# untitle2.net
KiCad netlist of a schematic drawn in EAGLE
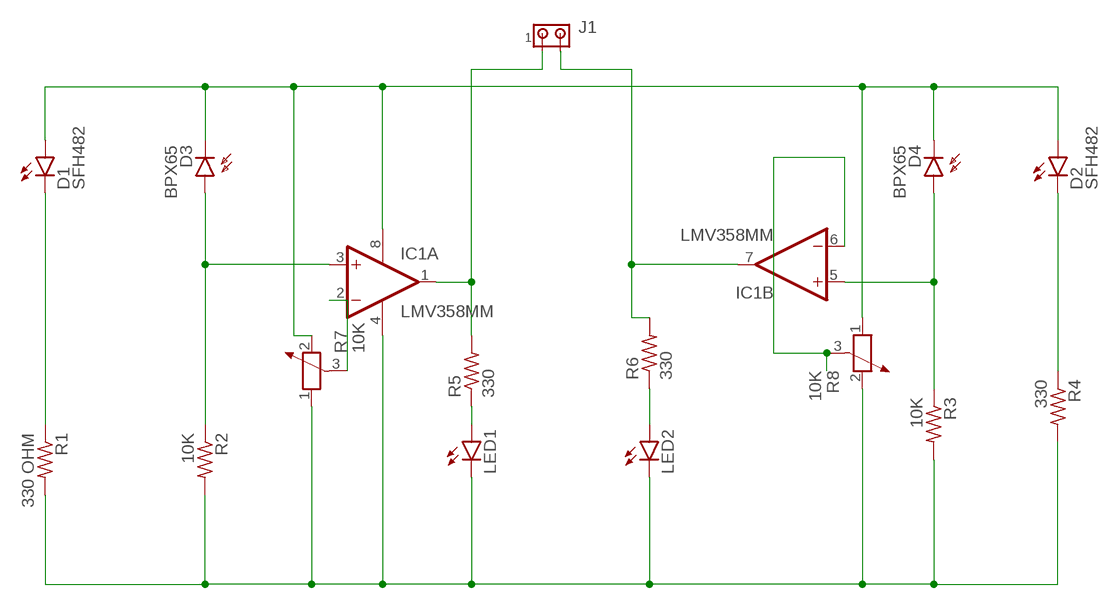
[diagram p0: schematic, sheet 1]

(export (version "E")
  (design (tool "Eeschema 10.0.6"))
  (components
    (comp (ref "D1")
      (value "SFH482")
      (footprint "eagle-import:SFH482")
      (libsource (lib "eagle-import") (part "SFH482"))
    )
    (comp (ref "D2")
      (value "SFH482")
      (footprint "eagle-import:SFH482")
      (libsource (lib "eagle-import") (part "SFH482"))
    )
    (comp (ref "D3")
      (value "BPX65")
      (footprint "eagle-import:BPX65")
      (fields (field (name "MPN") "BPX65."))
      (libsource (lib "eagle-import") (part "BPX65"))
    )
    (comp (ref "D4")
      (value "BPX65")
      (footprint "eagle-import:BPX65")
      (fields (field (name "MPN") "BPX65."))
      (libsource (lib "eagle-import") (part "BPX65"))
    )
    (comp (ref "IC1")
      (value "LMV358MM")
      (footprint "eagle-import:MSOP08")
      (libsource (lib "eagle-import") (part "LMV358?MM"))
    )
    (comp (ref "J1")
      (value "MTA02-100")
      (footprint "eagle-import:10X02MTA")
      (libsource (lib "eagle-import") (part "MTA02-100"))
    )
    (comp (ref "LED1")
      (value "LED3MM")
      (footprint "eagle-import:LED3MM")
      (libsource (lib "eagle-import") (part "LED3MM"))
    )
    (comp (ref "LED2")
      (value "LED3MM")
      (footprint "eagle-import:LED3MM")
      (libsource (lib "eagle-import") (part "LED3MM"))
    )
    (comp (ref "R1")
      (value "330 OHM")
      (footprint "eagle-import:0204V")
      (libsource (lib "eagle-import") (part "R-US_0204/2V"))
    )
    (comp (ref "R2")
      (value "10K")
      (footprint "eagle-import:0204V")
      (libsource (lib "eagle-import") (part "R-US_0204/2V"))
    )
    (comp (ref "R3")
      (value "10K")
      (footprint "eagle-import:0204V")
      (libsource (lib "eagle-import") (part "R-US_0204/2V"))
    )
    (comp (ref "R4")
      (value "330")
      (footprint "eagle-import:0204V")
      (libsource (lib "eagle-import") (part "R-US_0204/2V"))
    )
    (comp (ref "R5")
      (value "330")
      (footprint "eagle-import:0204V")
      (libsource (lib "eagle-import") (part "R-US_0204/2V"))
    )
    (comp (ref "R6")
      (value "330")
      (footprint "eagle-import:0204V")
      (libsource (lib "eagle-import") (part "R-US_0204/2V"))
    )
    (comp (ref "R7")
      (value "10K")
      (footprint "eagle-import:PT-10")
      (libsource (lib "eagle-import") (part "POTENTIOMETER_PT-10"))
    )
    (comp (ref "R8")
      (value "10K")
      (footprint "eagle-import:PT-10")
      (libsource (lib "eagle-import") (part "POTENTIOMETER_PT-10"))
    )
  )
  (nets
    (net (code "1") (name "Net-(D1-C)") (class "Default")
      (node (ref "D1") (pin "K") (pinfunction "C_K") (pintype "passive"))
      (node (ref "R1") (pin "1") (pinfunction "1_1") (pintype "passive"))
    )
    (net (code "2") (name "Net-(D2-C)") (class "Default")
      (node (ref "D2") (pin "K") (pinfunction "C_K") (pintype "passive"))
      (node (ref "R4") (pin "1") (pinfunction "1_1") (pintype "passive"))
    )
    (net (code "3") (name "Net-(D3-C)") (class "Default")
      (node (ref "D1") (pin "A") (pinfunction "A_A") (pintype "passive"))
      (node (ref "D2") (pin "A") (pinfunction "A_A") (pintype "passive"))
      (node (ref "D3") (pin "K") (pinfunction "C_K") (pintype "passive"))
      (node (ref "D4") (pin "K") (pinfunction "C_K") (pintype "passive"))
      (node (ref "IC1") (pin "8") (pinfunction "V+_8") (pintype "power_in"))
      (node (ref "R7") (pin "2") (pinfunction "2_2") (pintype "passive"))
      (node (ref "R8") (pin "1") (pinfunction "1_1") (pintype "passive"))
    )
    (net (code "4") (name "Net-(IC1A-+IN)") (class "Default")
      (node (ref "D3") (pin "A") (pinfunction "A_A") (pintype "passive"))
      (node (ref "IC1") (pin "3") (pinfunction "+IN_3") (pintype "input"))
      (node (ref "R2") (pin "1") (pinfunction "1_1") (pintype "passive"))
    )
    (net (code "5") (name "Net-(IC1A--IN)") (class "Default")
      (node (ref "IC1") (pin "2") (pinfunction "-IN_2") (pintype "input"))
      (node (ref "R7") (pin "3") (pinfunction "3_3") (pintype "passive"))
    )
    (net (code "6") (name "Net-(IC1A-OUT)") (class "Default")
      (node (ref "IC1") (pin "1") (pinfunction "OUT_1") (pintype "output"))
      (node (ref "J1") (pin "1") (pinfunction "1_1") (pintype "passive"))
      (node (ref "R5") (pin "2") (pinfunction "2_2") (pintype "passive"))
    )
    (net (code "7") (name "Net-(IC1B-+IN)") (class "Default")
      (node (ref "D4") (pin "A") (pinfunction "A_A") (pintype "passive"))
      (node (ref "IC1") (pin "5") (pinfunction "+IN_5") (pintype "input"))
      (node (ref "R3") (pin "1") (pinfunction "1_1") (pintype "passive"))
    )
    (net (code "8") (name "Net-(IC1B--IN)") (class "Default")
      (node (ref "IC1") (pin "6") (pinfunction "-IN_6") (pintype "input"))
      (node (ref "R8") (pin "3") (pinfunction "3_3") (pintype "passive"))
    )
    (net (code "9") (name "Net-(IC1B-OUT)") (class "Default")
      (node (ref "IC1") (pin "7") (pinfunction "OUT_7") (pintype "output"))
      (node (ref "J1") (pin "2") (pinfunction "2_2") (pintype "passive"))
      (node (ref "R6") (pin "2") (pinfunction "2_2") (pintype "passive"))
    )
    (net (code "10") (name "Net-(IC1C-V-)") (class "Default")
      (node (ref "IC1") (pin "4") (pinfunction "V-_4") (pintype "power_in"))
      (node (ref "LED1") (pin "K") (pinfunction "C_K") (pintype "passive"))
      (node (ref "LED2") (pin "K") (pinfunction "C_K") (pintype "passive"))
      (node (ref "R1") (pin "2") (pinfunction "2_2") (pintype "passive"))
      (node (ref "R2") (pin "2") (pinfunction "2_2") (pintype "passive"))
      (node (ref "R3") (pin "2") (pinfunction "2_2") (pintype "passive"))
      (node (ref "R4") (pin "2") (pinfunction "2_2") (pintype "passive"))
      (node (ref "R7") (pin "1") (pinfunction "1_1") (pintype "passive"))
      (node (ref "R8") (pin "2") (pinfunction "2_2") (pintype "passive"))
    )
    (net (code "11") (name "Net-(LED1-PadA)") (class "Default")
      (node (ref "LED1") (pin "A") (pinfunction "A_A") (pintype "passive"))
      (node (ref "R5") (pin "1") (pinfunction "1_1") (pintype "passive"))
    )
    (net (code "12") (name "Net-(LED2-PadA)") (class "Default")
      (node (ref "LED2") (pin "A") (pinfunction "A_A") (pintype "passive"))
      (node (ref "R6") (pin "1") (pinfunction "1_1") (pintype "passive"))
    )
  )
)
